# Instrumentation.net
KiCad netlist of a schematic drawn in Altium Designer
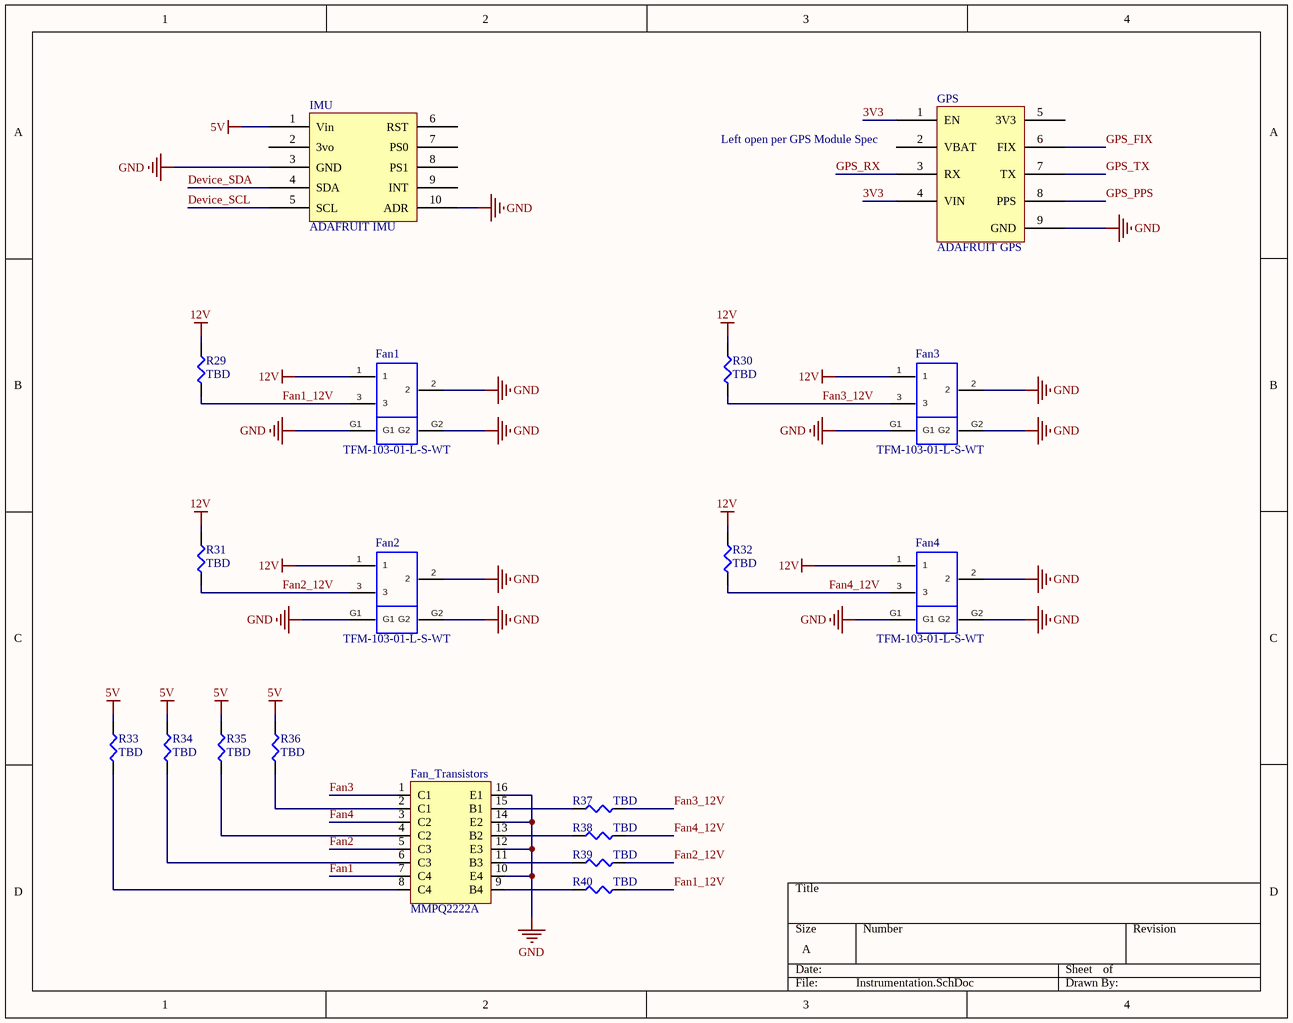
[diagram p0: Instrumentation.SchDoc]

(export (version "E")
  (design (tool "Eeschema 10.0.6"))
  (components
    (comp (ref "Fan1")
      (value "TFM-103-01-L-S-WT")
      (footprint "TFM-103-01-L-S-WT")
      (libsource (lib "MARCS Library Main") (part "TFM-103-01-L-S-WT"))
    )
    (comp (ref "Fan2")
      (value "TFM-103-01-L-S-WT")
      (footprint "TFM-103-01-L-S-WT")
      (libsource (lib "MARCS Library Main") (part "TFM-103-01-L-S-WT"))
    )
    (comp (ref "Fan3")
      (value "TFM-103-01-L-S-WT")
      (footprint "TFM-103-01-L-S-WT")
      (libsource (lib "MARCS Library Main") (part "TFM-103-01-L-S-WT"))
    )
    (comp (ref "Fan4")
      (value "TFM-103-01-L-S-WT")
      (footprint "TFM-103-01-L-S-WT")
      (libsource (lib "MARCS Library Main") (part "TFM-103-01-L-S-WT"))
    )
    (comp (ref "Fan_Transistors")
      (value "MMPQ2222A")
      (footprint "MMPQ2222A")
      (libsource (lib "MARCS Library Main") (part "MMPQ2222A"))
    )
    (comp (ref "GPS")
      (value "ADAFRUIT GPS")
      (footprint "ADAFRUIT ULTIMATE GPS")
      (libsource (lib "MARCS Library Main") (part "ADAFRUIT GPS"))
    )
    (comp (ref "IMU")
      (value "ADAFRUIT IMU")
      (footprint "ADAFRUIT IMU")
      (libsource (lib "MARCS Library Main") (part "ADAFRUIT IMU"))
    )
    (comp (ref "R29")
      (value "TBD")
      (footprint "0805R-GENERIC")
      (description "RESISTOR 0805 VALUE TO BE DETERMINED")
      (libsource (lib "MARCS Library Main") (part "0805R-TBD"))
    )
    (comp (ref "R30")
      (value "TBD")
      (footprint "0805R-GENERIC")
      (description "RESISTOR 0805 VALUE TO BE DETERMINED")
      (libsource (lib "MARCS Library Main") (part "0805R-TBD"))
    )
    (comp (ref "R31")
      (value "TBD")
      (footprint "0805R-GENERIC")
      (description "RESISTOR 0805 VALUE TO BE DETERMINED")
      (libsource (lib "MARCS Library Main") (part "0805R-TBD"))
    )
    (comp (ref "R32")
      (value "TBD")
      (footprint "0805R-GENERIC")
      (description "RESISTOR 0805 VALUE TO BE DETERMINED")
      (libsource (lib "MARCS Library Main") (part "0805R-TBD"))
    )
    (comp (ref "R33")
      (value "TBD")
      (footprint "0805R-GENERIC")
      (description "RESISTOR 0805 VALUE TO BE DETERMINED")
      (libsource (lib "MARCS Library Main") (part "0805R-TBD"))
    )
    (comp (ref "R34")
      (value "TBD")
      (footprint "0805R-GENERIC")
      (description "RESISTOR 0805 VALUE TO BE DETERMINED")
      (libsource (lib "MARCS Library Main") (part "0805R-TBD"))
    )
    (comp (ref "R35")
      (value "TBD")
      (footprint "0805R-GENERIC")
      (description "RESISTOR 0805 VALUE TO BE DETERMINED")
      (libsource (lib "MARCS Library Main") (part "0805R-TBD"))
    )
    (comp (ref "R36")
      (value "TBD")
      (footprint "0805R-GENERIC")
      (description "RESISTOR 0805 VALUE TO BE DETERMINED")
      (libsource (lib "MARCS Library Main") (part "0805R-TBD"))
    )
    (comp (ref "R37")
      (value "TBD")
      (footprint "0805R-GENERIC")
      (description "RESISTOR 0805 VALUE TO BE DETERMINED")
      (libsource (lib "MARCS Library Main") (part "0805R-TBD"))
    )
    (comp (ref "R38")
      (value "TBD")
      (footprint "0805R-GENERIC")
      (description "RESISTOR 0805 VALUE TO BE DETERMINED")
      (libsource (lib "MARCS Library Main") (part "0805R-TBD"))
    )
    (comp (ref "R39")
      (value "TBD")
      (footprint "0805R-GENERIC")
      (description "RESISTOR 0805 VALUE TO BE DETERMINED")
      (libsource (lib "MARCS Library Main") (part "0805R-TBD"))
    )
    (comp (ref "R40")
      (value "TBD")
      (footprint "0805R-GENERIC")
      (description "RESISTOR 0805 VALUE TO BE DETERMINED")
      (libsource (lib "MARCS Library Main") (part "0805R-TBD"))
    )
  )
  (nets
    (net (code "1") (name "/3V3") (class "Default")
      (node (ref "GPS") (pin "1") (pinfunction "EN_1") (pintype "passive"))
      (node (ref "GPS") (pin "4") (pinfunction "VIN_4") (pintype "power_in"))
    )
    (net (code "2") (name "/Device_SCL") (class "Default")
      (node (ref "IMU") (pin "5") (pinfunction "SCL_5") (pintype "passive"))
    )
    (net (code "3") (name "/Device_SDA") (class "Default")
      (node (ref "IMU") (pin "4") (pinfunction "SDA_4") (pintype "passive"))
    )
    (net (code "4") (name "/Fan1") (class "Default")
      (node (ref "Fan_Transistors") (pin "7") (pinfunction "C4_7") (pintype "passive"))
    )
    (net (code "5") (name "/Fan1_12V") (class "Default")
      (node (ref "Fan1") (pin "3") (pinfunction "3_3") (pintype "passive"))
      (node (ref "R29") (pin "2") (pintype "passive"))
      (node (ref "R40") (pin "2") (pintype "passive"))
    )
    (net (code "6") (name "/Fan2") (class "Default")
      (node (ref "Fan_Transistors") (pin "5") (pinfunction "C3_5") (pintype "passive"))
    )
    (net (code "7") (name "/Fan2_12V") (class "Default")
      (node (ref "Fan2") (pin "3") (pinfunction "3_3") (pintype "passive"))
      (node (ref "R31") (pin "2") (pintype "passive"))
      (node (ref "R39") (pin "2") (pintype "passive"))
    )
    (net (code "8") (name "/Fan3") (class "Default")
      (node (ref "Fan_Transistors") (pin "1") (pinfunction "C1_1") (pintype "passive"))
    )
    (net (code "9") (name "/Fan3_12V") (class "Default")
      (node (ref "Fan3") (pin "3") (pinfunction "3_3") (pintype "passive"))
      (node (ref "R30") (pin "2") (pintype "passive"))
      (node (ref "R37") (pin "2") (pintype "passive"))
    )
    (net (code "10") (name "/Fan4") (class "Default")
      (node (ref "Fan_Transistors") (pin "3") (pinfunction "C2_3") (pintype "passive"))
    )
    (net (code "11") (name "/Fan4_12V") (class "Default")
      (node (ref "Fan4") (pin "3") (pinfunction "3_3") (pintype "passive"))
      (node (ref "R32") (pin "2") (pintype "passive"))
      (node (ref "R38") (pin "2") (pintype "passive"))
    )
    (net (code "12") (name "/GPS_FIX") (class "Default")
      (node (ref "GPS") (pin "6") (pinfunction "FIX_6") (pintype "passive"))
    )
    (net (code "13") (name "/GPS_PPS") (class "Default")
      (node (ref "GPS") (pin "8") (pinfunction "PPS_8") (pintype "passive"))
    )
    (net (code "14") (name "/GPS_RX") (class "Default")
      (node (ref "GPS") (pin "3") (pinfunction "RX_3") (pintype "passive"))
    )
    (net (code "15") (name "/GPS_TX") (class "Default")
      (node (ref "GPS") (pin "7") (pinfunction "TX_7") (pintype "passive"))
    )
    (net (code "16") (name "5V") (class "Default")
      (node (ref "IMU") (pin "1") (pinfunction "Vin_1") (pintype "passive"))
      (node (ref "R33") (pin "1") (pintype "passive"))
      (node (ref "R34") (pin "1") (pintype "passive"))
      (node (ref "R35") (pin "1") (pintype "passive"))
      (node (ref "R36") (pin "1") (pintype "passive"))
    )
    (net (code "17") (name "12V") (class "Default")
      (node (ref "Fan1") (pin "1") (pinfunction "1_1") (pintype "passive"))
      (node (ref "Fan2") (pin "1") (pinfunction "1_1") (pintype "passive"))
      (node (ref "Fan3") (pin "1") (pinfunction "1_1") (pintype "passive"))
      (node (ref "Fan4") (pin "1") (pinfunction "1_1") (pintype "passive"))
      (node (ref "R29") (pin "1") (pintype "passive"))
      (node (ref "R30") (pin "1") (pintype "passive"))
      (node (ref "R31") (pin "1") (pintype "passive"))
      (node (ref "R32") (pin "1") (pintype "passive"))
    )
    (net (code "18") (name "GND") (class "Default")
      (node (ref "Fan1") (pin "2") (pinfunction "2_2") (pintype "passive"))
      (node (ref "Fan1") (pin "G1") (pinfunction "G1_G1") (pintype "passive"))
      (node (ref "Fan1") (pin "G2") (pinfunction "G2_G2") (pintype "passive"))
      (node (ref "Fan2") (pin "2") (pinfunction "2_2") (pintype "passive"))
      (node (ref "Fan2") (pin "G1") (pinfunction "G1_G1") (pintype "passive"))
      (node (ref "Fan2") (pin "G2") (pinfunction "G2_G2") (pintype "passive"))
      (node (ref "Fan3") (pin "2") (pinfunction "2_2") (pintype "passive"))
      (node (ref "Fan3") (pin "G1") (pinfunction "G1_G1") (pintype "passive"))
      (node (ref "Fan3") (pin "G2") (pinfunction "G2_G2") (pintype "passive"))
      (node (ref "Fan4") (pin "2") (pinfunction "2_2") (pintype "passive"))
      (node (ref "Fan4") (pin "G1") (pinfunction "G1_G1") (pintype "passive"))
      (node (ref "Fan4") (pin "G2") (pinfunction "G2_G2") (pintype "passive"))
      (node (ref "Fan_Transistors") (pin "10") (pinfunction "E4_10") (pintype "passive"))
      (node (ref "Fan_Transistors") (pin "12") (pinfunction "E3_12") (pintype "passive"))
      (node (ref "Fan_Transistors") (pin "14") (pinfunction "E2_14") (pintype "passive"))
      (node (ref "Fan_Transistors") (pin "16") (pinfunction "E1_16") (pintype "passive"))
      (node (ref "GPS") (pin "9") (pinfunction "GND_9") (pintype "power_in"))
      (node (ref "IMU") (pin "10") (pinfunction "ADR_10") (pintype "passive"))
      (node (ref "IMU") (pin "3") (pinfunction "GND_3") (pintype "passive"))
    )
    (net (code "19") (name "Net-(Fan_Transistors-B1)") (class "Default")
      (node (ref "Fan_Transistors") (pin "15") (pinfunction "B1_15") (pintype "passive"))
      (node (ref "R37") (pin "1") (pintype "passive"))
    )
    (net (code "20") (name "Net-(Fan_Transistors-B2)") (class "Default")
      (node (ref "Fan_Transistors") (pin "13") (pinfunction "B2_13") (pintype "passive"))
      (node (ref "R38") (pin "1") (pintype "passive"))
    )
    (net (code "21") (name "Net-(Fan_Transistors-B3)") (class "Default")
      (node (ref "Fan_Transistors") (pin "11") (pinfunction "B3_11") (pintype "passive"))
      (node (ref "R39") (pin "1") (pintype "passive"))
    )
    (net (code "22") (name "Net-(Fan_Transistors-B4)") (class "Default")
      (node (ref "Fan_Transistors") (pin "9") (pinfunction "B4_9") (pintype "passive"))
      (node (ref "R40") (pin "1") (pintype "passive"))
    )
    (net (code "23") (name "Net-(Fan_Transistors-C1-Pad2)") (class "Default")
      (node (ref "Fan_Transistors") (pin "2") (pinfunction "C1_2") (pintype "passive"))
      (node (ref "R36") (pin "2") (pintype "passive"))
    )
    (net (code "24") (name "Net-(Fan_Transistors-C2-Pad4)") (class "Default")
      (node (ref "Fan_Transistors") (pin "4") (pinfunction "C2_4") (pintype "passive"))
      (node (ref "R35") (pin "2") (pintype "passive"))
    )
    (net (code "25") (name "Net-(Fan_Transistors-C3-Pad6)") (class "Default")
      (node (ref "Fan_Transistors") (pin "6") (pinfunction "C3_6") (pintype "passive"))
      (node (ref "R34") (pin "2") (pintype "passive"))
    )
    (net (code "26") (name "Net-(Fan_Transistors-C4-Pad8)") (class "Default")
      (node (ref "Fan_Transistors") (pin "8") (pinfunction "C4_8") (pintype "passive"))
      (node (ref "R33") (pin "2") (pintype "passive"))
    )
    (net (code "27") (name "unconnected-(GPS-3V3-Pad5)") (class "Default")
      (node (ref "GPS") (pin "5") (pinfunction "3V3_5") (pintype "power_in"))
    )
    (net (code "28") (name "unconnected-(GPS-VBAT-Pad2)") (class "Default")
      (node (ref "GPS") (pin "2") (pinfunction "VBAT_2") (pintype "power_in"))
    )
    (net (code "29") (name "unconnected-(IMU-3vo-Pad2)") (class "Default")
      (node (ref "IMU") (pin "2") (pinfunction "3vo_2") (pintype "passive"))
    )
    (net (code "30") (name "unconnected-(IMU-INT-Pad9)") (class "Default")
      (node (ref "IMU") (pin "9") (pinfunction "INT_9") (pintype "passive"))
    )
    (net (code "31") (name "unconnected-(IMU-PS0-Pad7)") (class "Default")
      (node (ref "IMU") (pin "7") (pinfunction "PS0_7") (pintype "passive"))
    )
    (net (code "32") (name "unconnected-(IMU-PS1-Pad8)") (class "Default")
      (node (ref "IMU") (pin "8") (pinfunction "PS1_8") (pintype "passive"))
    )
    (net (code "33") (name "unconnected-(IMU-RST-Pad6)") (class "Default")
      (node (ref "IMU") (pin "6") (pinfunction "RST_6") (pintype "passive"))
    )
  )
)
